# RFA433.net
KiCad netlist of a schematic drawn in Altium Designer
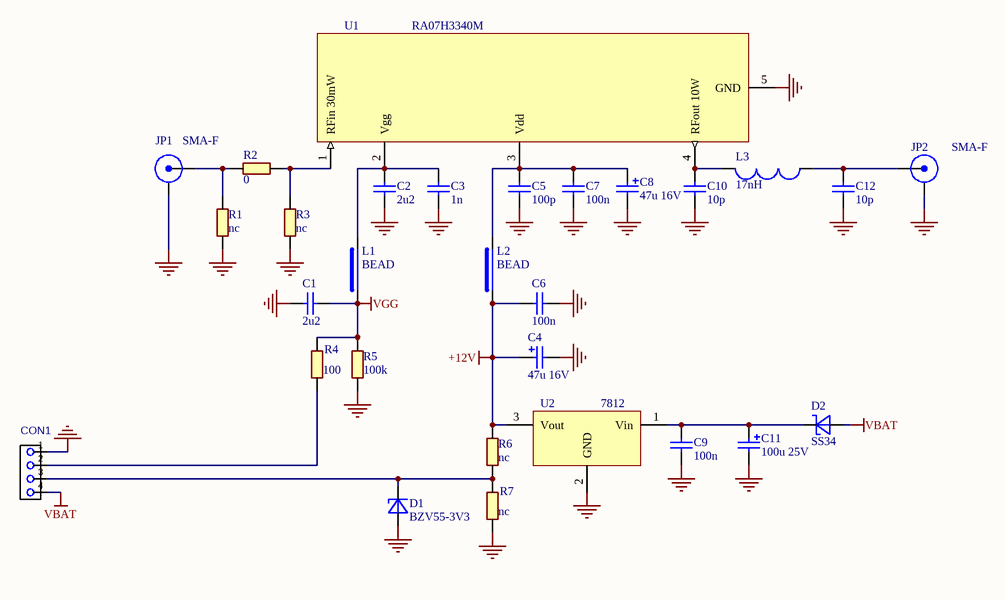
[diagram p0: RFA433.SchDoc]

(export (version "E")
  (design (tool "Eeschema 10.0.6"))
  (components
    (comp (ref "C1")
      (value "2u2")
      (footprint "C-0805")
      (fields (field (name "VOLTAGE") "50V"))
      (libsource (lib "Passive") (part "CAPN"))
    )
    (comp (ref "C2")
      (value "2u2")
      (footprint "C-0805")
      (fields (field (name "VOLTAGE") "50V"))
      (libsource (lib "Passive") (part "CAPN"))
    )
    (comp (ref "C3")
      (value "1n")
      (footprint "C-0805")
      (fields (field (name "VOLTAGE") "50V"))
      (libsource (lib "Passive") (part "CAPN"))
    )
    (comp (ref "C4")
      (value "47u 16V")
      (footprint "ECAPSMD6377")
      (fields (field (name "VOLTAGE") "16V"))
      (libsource (lib "Passive") (part "CAPP_1"))
    )
    (comp (ref "C5")
      (value "100p")
      (footprint "C-0805")
      (fields (field (name "VOLTAGE") "50V"))
      (libsource (lib "Passive") (part "CAPN"))
    )
    (comp (ref "C6")
      (value "100n")
      (footprint "C-0805")
      (fields (field (name "VOLTAGE") "50V"))
      (libsource (lib "Passive") (part "CAPN"))
    )
    (comp (ref "C7")
      (value "100n")
      (footprint "C-0805")
      (fields (field (name "VOLTAGE") "50V"))
      (libsource (lib "Passive") (part "CAPN"))
    )
    (comp (ref "C8")
      (value "47u 16V")
      (footprint "ECAPSMD6377")
      (fields (field (name "VOLTAGE") "16V"))
      (libsource (lib "Passive") (part "CAPP_1"))
    )
    (comp (ref "C9")
      (value "100n")
      (footprint "C-0805")
      (fields (field (name "VOLTAGE") "50V"))
      (libsource (lib "Passive") (part "CAPN"))
    )
    (comp (ref "C10")
      (value "10p")
      (footprint "C-0805")
      (fields (field (name "VOLTAGE") "50V"))
      (libsource (lib "Passive") (part "CAPN"))
    )
    (comp (ref "C11")
      (value "100u 25V")
      (footprint "ECAPSMD6377")
      (fields (field (name "VOLTAGE") "16V"))
      (libsource (lib "Passive") (part "CAPP_1"))
    )
    (comp (ref "C12")
      (value "10p")
      (footprint "C-0805")
      (fields (field (name "VOLTAGE") "50V"))
      (libsource (lib "Passive") (part "CAPN"))
    )
    (comp (ref "CON1")
      (value "KLS2-301-5.0-04P")
      (footprint "KLS2-301-5.0-04P")
      (libsource (lib "CLAP") (part "KLS2-301-5.0-04P"))
    )
    (comp (ref "D1") (value "BZV55-3V3") (footprint "SOD-80_NUM") (libsource (lib "Diodes") (part "DIODZ")))
    (comp (ref "D2") (value "SS34") (footprint "D_SMC") (libsource (lib "Diodes") (part "DIODSH")))
    (comp (ref "JP1")
      (value "SMA-F")
      (footprint "AMPHENOL_132357-11")
      (description "RF Connector")
      (libsource (lib "Connectors") (part "RF connector"))
    )
    (comp (ref "JP2")
      (value "SMA-F")
      (footprint "AMPHENOL_132357-11")
      (description "RF Connector")
      (libsource (lib "Connectors") (part "RF connector"))
    )
    (comp (ref "L1") (value "BEAD") (footprint "R-1206") (libsource (lib "Passive") (part "BEAD")))
    (comp (ref "L2") (value "BEAD") (footprint "R-1206") (libsource (lib "Passive") (part "BEAD")))
    (comp (ref "L3") (value "17nH") (footprint "2.75TD3.0W0.7_SMD") (libsource (lib "Passive") (part "L")))
    (comp (ref "R1") (value "nc") (footprint "R-0805") (libsource (lib "Passive") (part "RES")))
    (comp (ref "R2") (value "0") (footprint "R-0805") (libsource (lib "") (part "RES_1")))
    (comp (ref "R3") (value "nc") (footprint "R-0805") (libsource (lib "Passive") (part "RES")))
    (comp (ref "R4") (value "100") (footprint "R-0805") (libsource (lib "Passive") (part "RES")))
    (comp (ref "R5") (value "100k") (footprint "R-0805") (libsource (lib "Passive") (part "RES")))
    (comp (ref "R6") (value "nc") (footprint "R-0805") (libsource (lib "Passive") (part "RES")))
    (comp (ref "R7") (value "nc") (footprint "R-0805") (libsource (lib "Passive") (part "RES")))
    (comp (ref "U1")
      (value "RA07H3340M")
      (footprint "H46")
      (description "RF pwer amplifier")
      (libsource (lib "RCS-IMS") (part "RA07H3340M"))
    )
    (comp (ref "U2")
      (value "7812")
      (footprint "TO-220/HOR_FLAT")
      (description "12V voltage regulator")
      (libsource (lib "ICs") (part "7805"))
    )
  )
  (nets
    (net (code "1") (name "+12V") (class "Default")
      (node (ref "C4") (pin "1") (pinfunction "1_1") (pintype "passive"))
      (node (ref "C6") (pin "1") (pinfunction "1_1") (pintype "passive"))
      (node (ref "L2") (pin "1") (pinfunction "1_1") (pintype "passive"))
      (node (ref "R6") (pin "2") (pinfunction "2_2") (pintype "passive"))
      (node (ref "U2") (pin "3") (pinfunction "Vout_3") (pintype "power_in"))
    )
    (net (code "2") (name "GND") (class "Default")
      (node (ref "C1") (pin "1") (pinfunction "1_1") (pintype "passive"))
      (node (ref "C10") (pin "2") (pinfunction "2_2") (pintype "passive"))
      (node (ref "C11") (pin "2") (pinfunction "1_2") (pintype "passive"))
      (node (ref "C12") (pin "2") (pinfunction "2_2") (pintype "passive"))
      (node (ref "C2") (pin "2") (pinfunction "2_2") (pintype "passive"))
      (node (ref "C3") (pin "2") (pinfunction "2_2") (pintype "passive"))
      (node (ref "C4") (pin "2") (pinfunction "1_2") (pintype "passive"))
      (node (ref "C5") (pin "2") (pinfunction "2_2") (pintype "passive"))
      (node (ref "C6") (pin "2") (pinfunction "2_2") (pintype "passive"))
      (node (ref "C7") (pin "2") (pinfunction "2_2") (pintype "passive"))
      (node (ref "C8") (pin "2") (pinfunction "1_2") (pintype "passive"))
      (node (ref "C9") (pin "1") (pinfunction "1_1") (pintype "passive"))
      (node (ref "CON1") (pin "1") (pintype "passive"))
      (node (ref "D1") (pin "1") (pinfunction "1_1") (pintype "passive"))
      (node (ref "JP1") (pin "2") (pinfunction "Y_2") (pintype "passive"))
      (node (ref "JP2") (pin "2") (pinfunction "Y_2") (pintype "passive"))
      (node (ref "R1") (pin "1") (pinfunction "1_1") (pintype "passive"))
      (node (ref "R3") (pin "1") (pinfunction "1_1") (pintype "passive"))
      (node (ref "R5") (pin "1") (pinfunction "1_1") (pintype "passive"))
      (node (ref "R7") (pin "1") (pinfunction "1_1") (pintype "passive"))
      (node (ref "U1") (pin "5") (pinfunction "GND_5") (pintype "power_in"))
      (node (ref "U2") (pin "2") (pinfunction "GND_2") (pintype "power_in"))
    )
    (net (code "3") (name "Net-(CON1-Pad2)") (class "Default")
      (node (ref "CON1") (pin "2") (pintype "passive"))
      (node (ref "R4") (pin "1") (pinfunction "1_1") (pintype "passive"))
    )
    (net (code "4") (name "Net-(CON1-Pad3)") (class "Default")
      (node (ref "CON1") (pin "3") (pintype "passive"))
      (node (ref "D1") (pin "2") (pinfunction "2_2") (pintype "passive"))
      (node (ref "R6") (pin "1") (pinfunction "1_1") (pintype "passive"))
      (node (ref "R7") (pin "2") (pinfunction "2_2") (pintype "passive"))
    )
    (net (code "5") (name "Net-(JP1-X)") (class "Default")
      (node (ref "JP1") (pin "1") (pinfunction "X_1") (pintype "passive"))
      (node (ref "R1") (pin "2") (pinfunction "2_2") (pintype "passive"))
      (node (ref "R2") (pin "1") (pinfunction "1_1") (pintype "passive"))
    )
    (net (code "6") (name "Net-(JP2-X)") (class "Default")
      (node (ref "C12") (pin "1") (pinfunction "1_1") (pintype "passive"))
      (node (ref "JP2") (pin "1") (pinfunction "X_1") (pintype "passive"))
      (node (ref "L3") (pin "1") (pinfunction "1_1") (pintype "passive"))
    )
    (net (code "7") (name "Net-(U1-RFin_30mW)") (class "Default")
      (node (ref "R2") (pin "2") (pinfunction "2_2") (pintype "passive"))
      (node (ref "R3") (pin "2") (pinfunction "2_2") (pintype "passive"))
      (node (ref "U1") (pin "1") (pinfunction "RFin_30mW_1") (pintype "input"))
    )
    (net (code "8") (name "Net-(U1-RFout_10W)") (class "Default")
      (node (ref "C10") (pin "1") (pinfunction "1_1") (pintype "passive"))
      (node (ref "L3") (pin "2") (pinfunction "2_2") (pintype "passive"))
      (node (ref "U1") (pin "4") (pinfunction "RFout_10W_4") (pintype "output"))
    )
    (net (code "9") (name "Net-(U1-Vdd)") (class "Default")
      (node (ref "C5") (pin "1") (pinfunction "1_1") (pintype "passive"))
      (node (ref "C7") (pin "1") (pinfunction "1_1") (pintype "passive"))
      (node (ref "C8") (pin "1") (pinfunction "1_1") (pintype "passive"))
      (node (ref "L2") (pin "2") (pinfunction "2_2") (pintype "passive"))
      (node (ref "U1") (pin "3") (pinfunction "Vdd_3") (pintype "power_in"))
    )
    (net (code "10") (name "Net-(U1-Vgg)") (class "Default")
      (node (ref "C2") (pin "1") (pinfunction "1_1") (pintype "passive"))
      (node (ref "C3") (pin "1") (pinfunction "1_1") (pintype "passive"))
      (node (ref "L1") (pin "2") (pinfunction "2_2") (pintype "passive"))
      (node (ref "U1") (pin "2") (pinfunction "Vgg_2") (pintype "power_in"))
    )
    (net (code "11") (name "Net-(U2-Vin)") (class "Default")
      (node (ref "C11") (pin "1") (pinfunction "1_1") (pintype "passive"))
      (node (ref "C9") (pin "2") (pinfunction "2_2") (pintype "passive"))
      (node (ref "D2") (pin "2") (pinfunction "2_2") (pintype "passive"))
      (node (ref "U2") (pin "1") (pinfunction "Vin_1") (pintype "power_in"))
    )
    (net (code "12") (name "VBAT") (class "Default")
      (node (ref "CON1") (pin "4") (pintype "passive"))
      (node (ref "D2") (pin "1") (pinfunction "1_1") (pintype "passive"))
    )
    (net (code "13") (name "VGG") (class "Default")
      (node (ref "C1") (pin "2") (pinfunction "2_2") (pintype "passive"))
      (node (ref "L1") (pin "1") (pinfunction "1_1") (pintype "passive"))
      (node (ref "R4") (pin "2") (pinfunction "2_2") (pintype "passive"))
      (node (ref "R5") (pin "2") (pinfunction "2_2") (pintype "passive"))
    )
  )
)
